# ESP32_RC522_ACS712_NUTNHAN_RELAY.net
KiCad netlist of a schematic drawn in EasyEDA
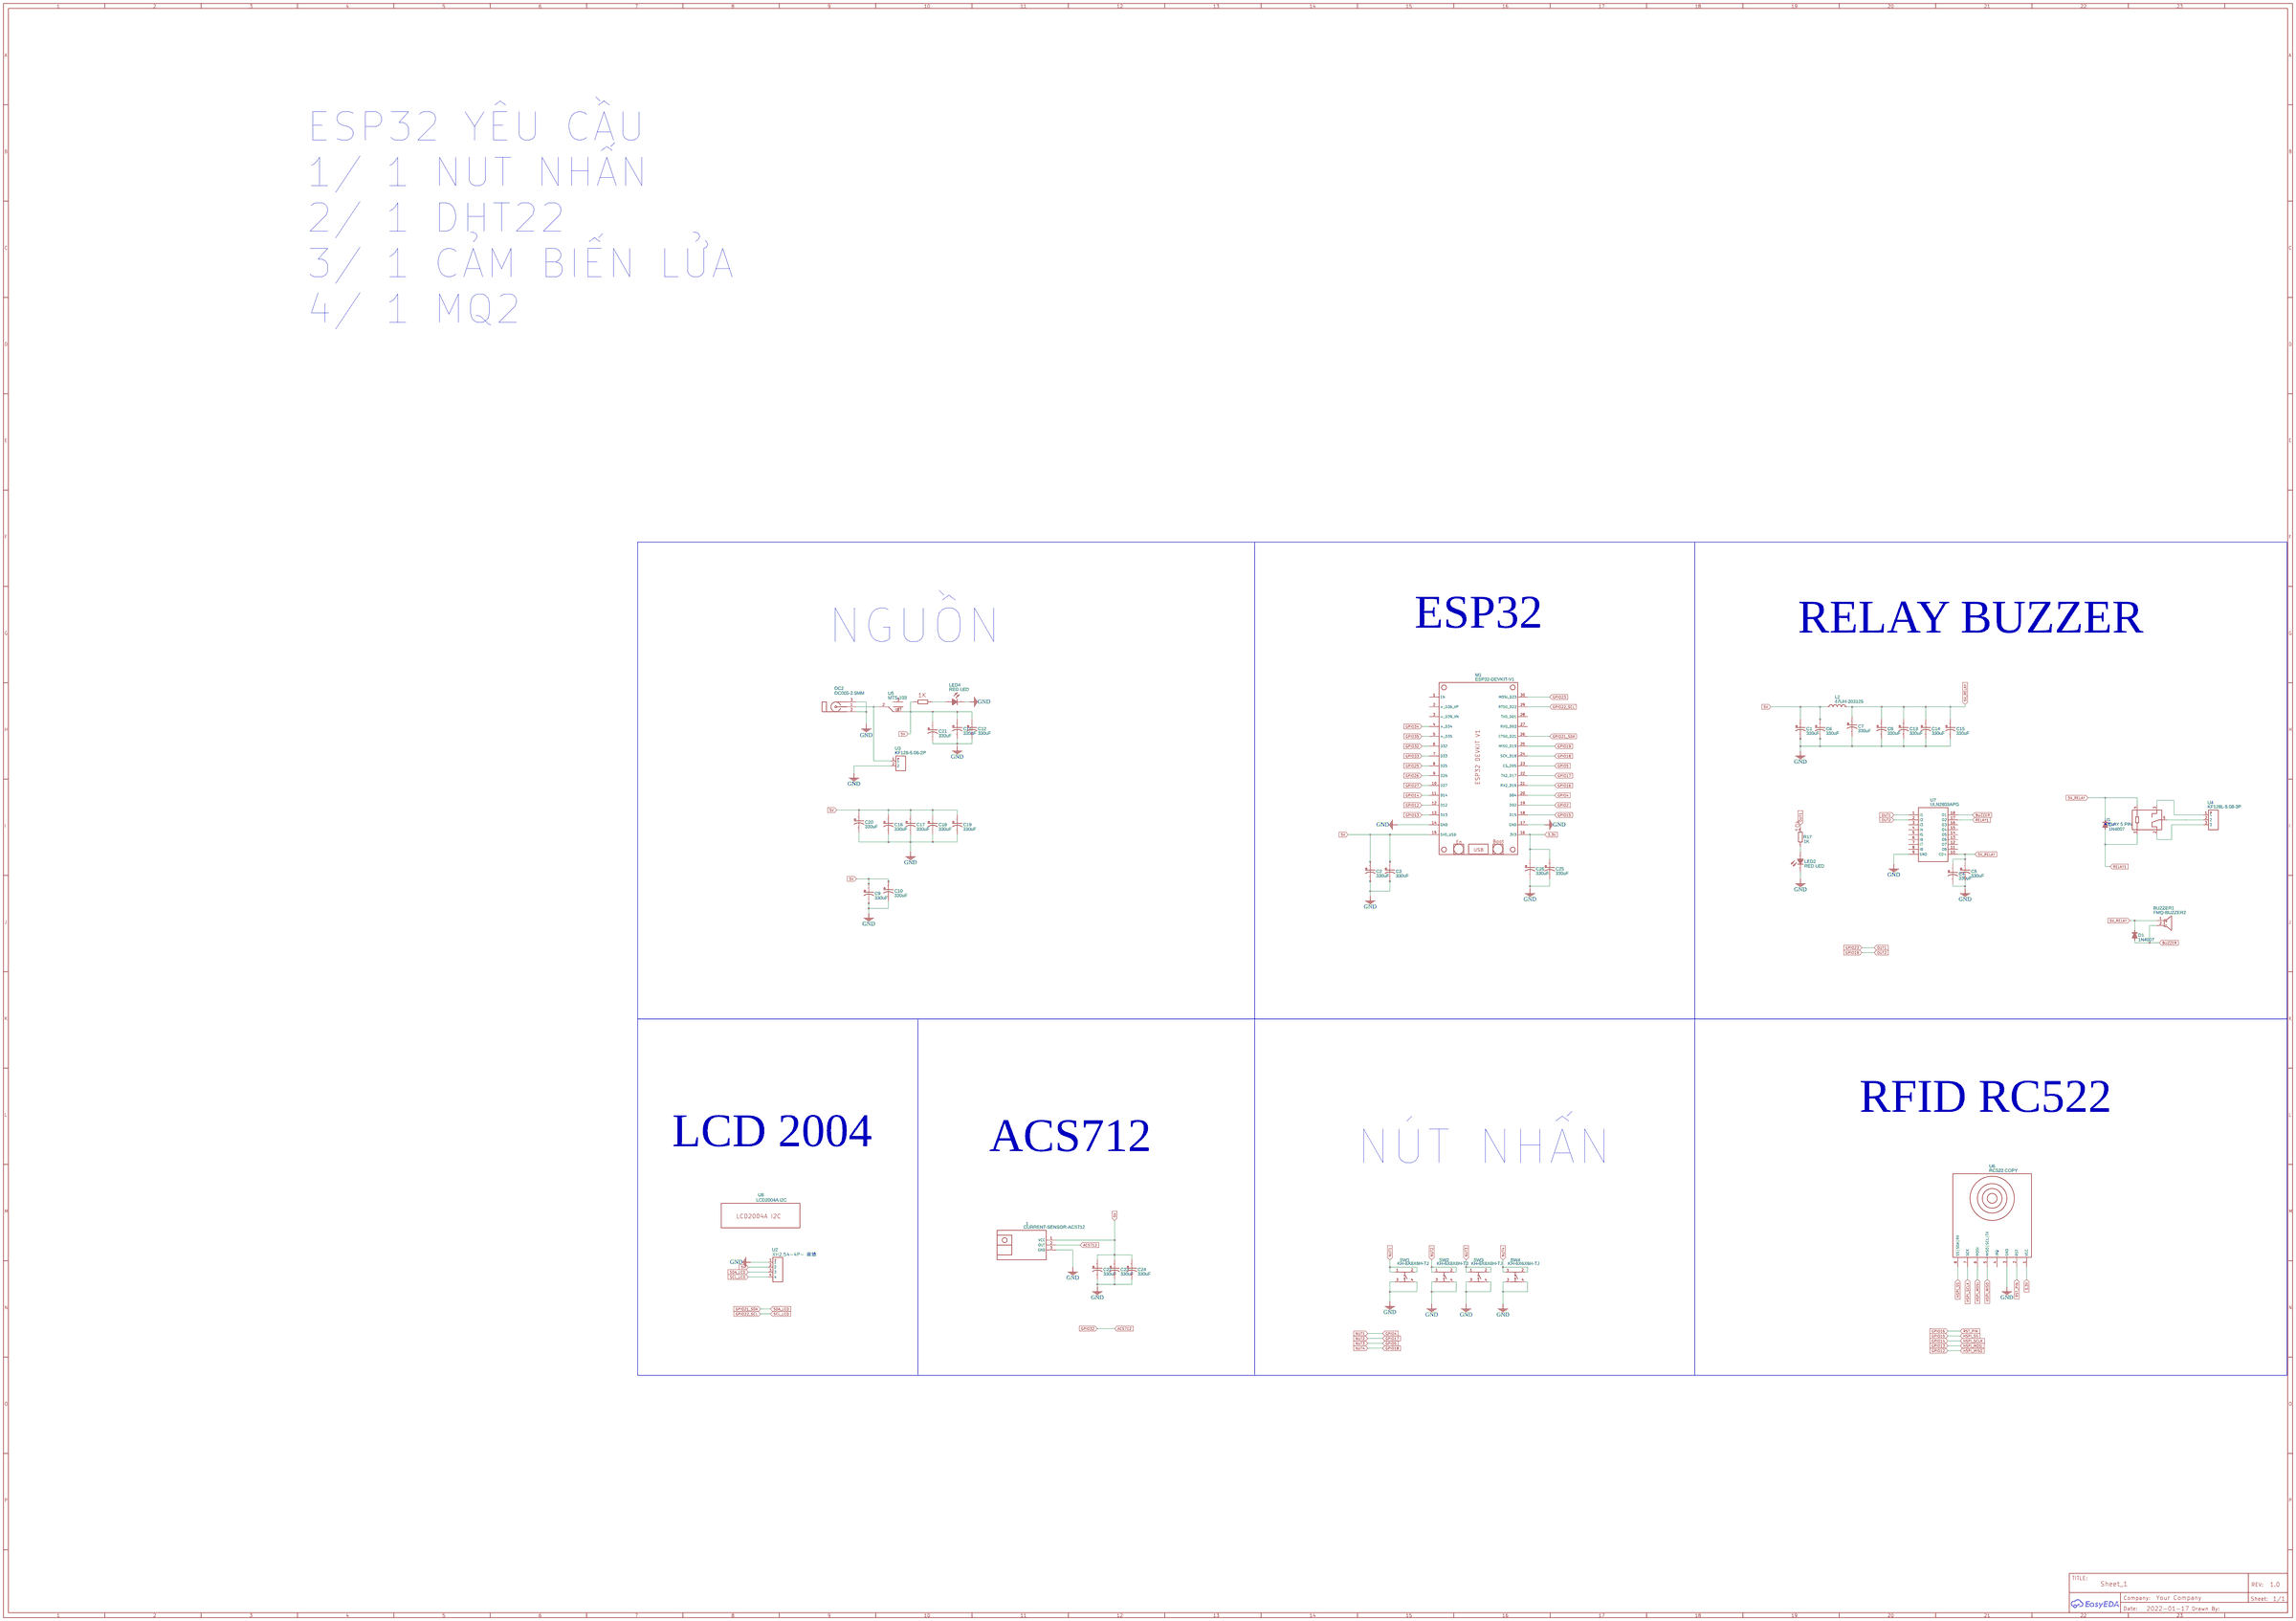
[diagram p0: schematic sheet]

(export (version "E")
  (design (tool "Eeschema 10.0.6"))
  (components
    (comp (ref "1") (value "CURRENT-SENSOR-ACS712") (libsource (lib "") (part "CURRENT-SENSOR-ACS712")))
    (comp (ref "BUZZER1")
      (value "FMQ-BUZZER2")
      (fields (field (name "BOM_Supplier Part") "C9900006103"))
      (libsource (lib "") (part "FMQ-BUZZER2"))
    )
    (comp (ref "C1")
      (value "330uF")
      (fields (field (name "BOM_Supplier Part") "C165541"))
      (libsource (lib "") (part "NXA 16V330 8*11.5"))
    )
    (comp (ref "C2")
      (value "330uF")
      (fields (field (name "BOM_Supplier Part") "C165541"))
      (libsource (lib "") (part "NXA 16V330 8*11.5"))
    )
    (comp (ref "C3")
      (value "330uF")
      (fields (field (name "BOM_Supplier Part") "C165541"))
      (libsource (lib "") (part "NXA 16V330 8*11.5"))
    )
    (comp (ref "C4")
      (value "330uF")
      (fields (field (name "BOM_Supplier Part") "C165541"))
      (libsource (lib "") (part "NXA 16V330 8*11.5"))
    )
    (comp (ref "C5")
      (value "330uF")
      (fields (field (name "BOM_Supplier Part") "C165541"))
      (libsource (lib "") (part "NXA 16V330 8*11.5"))
    )
    (comp (ref "C6")
      (value "330uF")
      (fields (field (name "BOM_Supplier Part") "C165541"))
      (libsource (lib "") (part "NXA 16V330 8*11.5"))
    )
    (comp (ref "C7")
      (value "330uF")
      (fields (field (name "BOM_Supplier Part") "C165541"))
      (libsource (lib "") (part "NXA 16V330 8*11.5"))
    )
    (comp (ref "C8")
      (value "330uF")
      (fields (field (name "BOM_Supplier Part") "C165541"))
      (libsource (lib "") (part "NXA 16V330 8*11.5"))
    )
    (comp (ref "C9")
      (value "330uF")
      (fields (field (name "BOM_Supplier Part") "C165541"))
      (libsource (lib "") (part "NXA 16V330 8*11.5"))
    )
    (comp (ref "C10")
      (value "330uF")
      (fields (field (name "BOM_Supplier Part") "C165541"))
      (libsource (lib "") (part "NXA 16V330 8*11.5"))
    )
    (comp (ref "C11")
      (value "330uF")
      (fields (field (name "BOM_Supplier Part") "C165541"))
      (libsource (lib "") (part "NXA 16V330 8*11.5"))
    )
    (comp (ref "C12")
      (value "330uF")
      (fields (field (name "BOM_Supplier Part") "C165541"))
      (libsource (lib "") (part "NXA 16V330 8*11.5"))
    )
    (comp (ref "C13")
      (value "330uF")
      (fields (field (name "BOM_Supplier Part") "C165541"))
      (libsource (lib "") (part "NXA 16V330 8*11.5"))
    )
    (comp (ref "C14")
      (value "330uF")
      (fields (field (name "BOM_Supplier Part") "C165541"))
      (libsource (lib "") (part "NXA 16V330 8*11.5"))
    )
    (comp (ref "C15")
      (value "330uF")
      (fields (field (name "BOM_Supplier Part") "C165541"))
      (libsource (lib "") (part "NXA 16V330 8*11.5"))
    )
    (comp (ref "C16")
      (value "330uF")
      (fields (field (name "BOM_Supplier Part") "C165541"))
      (libsource (lib "") (part "NXA 16V330 8*11.5"))
    )
    (comp (ref "C17")
      (value "330uF")
      (fields (field (name "BOM_Supplier Part") "C165541"))
      (libsource (lib "") (part "NXA 16V330 8*11.5"))
    )
    (comp (ref "C18")
      (value "330uF")
      (fields (field (name "BOM_Supplier Part") "C165541"))
      (libsource (lib "") (part "NXA 16V330 8*11.5"))
    )
    (comp (ref "C19")
      (value "330uF")
      (fields (field (name "BOM_Supplier Part") "C165541"))
      (libsource (lib "") (part "NXA 16V330 8*11.5"))
    )
    (comp (ref "C20")
      (value "330uF")
      (fields (field (name "BOM_Supplier Part") "C165541"))
      (libsource (lib "") (part "NXA 16V330 8*11.5"))
    )
    (comp (ref "C21")
      (value "330uF")
      (fields (field (name "BOM_Supplier Part") "C165541"))
      (libsource (lib "") (part "NXA 16V330 8*11.5"))
    )
    (comp (ref "C22")
      (value "330uF")
      (fields (field (name "BOM_Supplier Part") "C165541"))
      (libsource (lib "") (part "NXA 16V330 8*11.5_1"))
    )
    (comp (ref "C23")
      (value "330uF")
      (fields (field (name "BOM_Supplier Part") "C165541"))
      (libsource (lib "") (part "NXA 16V330 8*11.5_1"))
    )
    (comp (ref "C24")
      (value "330uF")
      (fields (field (name "BOM_Supplier Part") "C165541"))
      (libsource (lib "") (part "NXA 16V330 8*11.5_1"))
    )
    (comp (ref "C25")
      (value "330uF")
      (fields (field (name "BOM_Supplier Part") "C165541"))
      (libsource (lib "") (part "NXA 16V330 8*11.5"))
    )
    (comp (ref "C26")
      (value "330uF")
      (fields (field (name "BOM_Supplier Part") "C165541"))
      (libsource (lib "") (part "NXA 16V330 8*11.5"))
    )
    (comp (ref "D1") (value "1N4007") (libsource (lib "") (part "1N4007")))
    (comp (ref "D4") (value "1N4007") (libsource (lib "") (part "1N4007")))
    (comp (ref "DC2")
      (value "DC005-2.5MM")
      (fields (field (name "BOM_Supplier Part") "C111573"))
      (libsource (lib "") (part "DC005-2.5MM"))
    )
    (comp (ref "L2")
      (value "47UH-203125")
      (fields
        (field (name "BOM_Manufacturer Part") "47uH-203125")
        (field (name "BOM_Supplier Part") "C9900004701")
      )
      (libsource (lib "") (part "47UH-203125"))
    )
    (comp (ref "LED2")
      (value "RED LED")
      (fields
        (field (name "BOM_Manufacturer Part") "333-2SURD/S530-A3")
        (field (name "BOM_Supplier Part") "C87271")
      )
      (libsource (lib "") (part "RED LED"))
    )
    (comp (ref "LED4")
      (value "RED LED")
      (fields
        (field (name "BOM_Manufacturer Part") "333-2SURD/S530-A3")
        (field (name "BOM_Supplier Part") "C87271")
      )
      (libsource (lib "") (part "RED LED_1"))
    )
    (comp (ref "M1")
      (value "ESP32-DEVKIT-V1")
      (fields (field (name "BOM_Manufacturer Part") "ESP32 Module - Doit.am"))
      (libsource (lib "") (part "ESP32-DEVKIT-V1"))
    )
    (comp (ref "R2")
      (value "1K")
      (fields
        (field (name "BOM_Manufacturer Part") "EWWR0003J1K00T9")
        (field (name "BOM_Supplier Part") "C348856")
      )
      (libsource (lib "") (part "resistor 10k ohm_1"))
    )
    (comp (ref "R17")
      (value "1K")
      (fields
        (field (name "BOM_Manufacturer Part") "EWWR0003J1K00T9")
        (field (name "BOM_Supplier Part") "C348856")
      )
      (libsource (lib "") (part "resistor 10k ohm"))
    )
    (comp (ref "SW1")
      (value "KH-6X6X6H-TJ")
      (fields (field (name "BOM_Supplier Part") "C2837516"))
      (libsource (lib "") (part "KH-6X6X6H-TJ"))
    )
    (comp (ref "SW2")
      (value "KH-6X6X6H-TJ")
      (fields (field (name "BOM_Supplier Part") "C2837516"))
      (libsource (lib "") (part "KH-6X6X6H-TJ"))
    )
    (comp (ref "SW3")
      (value "KH-6X6X6H-TJ")
      (fields (field (name "BOM_Supplier Part") "C2837516"))
      (libsource (lib "") (part "KH-6X6X6H-TJ"))
    )
    (comp (ref "SW4")
      (value "KH-6X6X6H-TJ")
      (fields (field (name "BOM_Supplier Part") "C2837516"))
      (libsource (lib "") (part "KH-6X6X6H-TJ"))
    )
    (comp (ref "U1") (value "RELAY 5 PIN") (libsource (lib "") (part "RELAY 5 PIN")))
    (comp (ref "U2")
      (value "XH2.54-4P- 直插")
      (fields (field (name "BOM_Supplier Part") "C9900000103"))
      (libsource (lib "") (part "XH2.54-4P- 直插"))
    )
    (comp (ref "U3")
      (value "KF128-5.08-2P")
      (fields (field (name "BOM_Supplier Part") "C474952"))
      (libsource (lib "") (part "KF128-5.08-2P"))
    )
    (comp (ref "U4")
      (value "KF128L-5.08-3P")
      (fields (field (name "BOM_Supplier Part") "C474941"))
      (libsource (lib "") (part "KF128L-5.08-3P"))
    )
    (comp (ref "U5") (value "MTS-103") (libsource (lib "") (part "MTS-103")))
    (comp (ref "U6") (value "RC522 COPY") (libsource (lib "") (part "RC522 COPY")))
    (comp (ref "U7")
      (value "ULN2803APG")
      (fields (field (name "BOM_Supplier Part") "C5252"))
      (libsource (lib "") (part "ULN2803APG"))
    )
    (comp (ref "U8")
      (value "LCD2004A I2C")
      (fields (field (name "BOM_Manufacturer Part") "LCD2004A"))
      (libsource (lib "") (part "LCD2004A I2C"))
    )
  )
  (nets
    (net (code "1") (name "3.3V") (class "Default")
      (node (ref "C25") (pin "1") (pinfunction "1_1") (pintype "unspecified"))
      (node (ref "C26") (pin "1") (pinfunction "1_1") (pintype "unspecified"))
      (node (ref "M1") (pin "16") (pinfunction "3V3_16") (pintype "unspecified"))
      (node (ref "U6") (pin "1") (pinfunction "VCC_1") (pintype "unspecified"))
    )
    (net (code "2") (name "5V") (class "Default")
      (node (ref "1") (pin "1") (pinfunction "VCC_1") (pintype "bidirectional"))
      (node (ref "C1") (pin "1") (pinfunction "1_1") (pintype "unspecified"))
      (node (ref "C10") (pin "1") (pinfunction "1_1") (pintype "unspecified"))
      (node (ref "C11") (pin "1") (pinfunction "1_1") (pintype "unspecified"))
      (node (ref "C12") (pin "1") (pinfunction "1_1") (pintype "unspecified"))
      (node (ref "C16") (pin "1") (pinfunction "1_1") (pintype "unspecified"))
      (node (ref "C17") (pin "1") (pinfunction "1_1") (pintype "unspecified"))
      (node (ref "C18") (pin "1") (pinfunction "1_1") (pintype "unspecified"))
      (node (ref "C19") (pin "1") (pinfunction "1_1") (pintype "unspecified"))
      (node (ref "C2") (pin "1") (pinfunction "1_1") (pintype "unspecified"))
      (node (ref "C20") (pin "1") (pinfunction "1_1") (pintype "unspecified"))
      (node (ref "C21") (pin "1") (pinfunction "1_1") (pintype "unspecified"))
      (node (ref "C22") (pin "1") (pinfunction "1_1") (pintype "unspecified"))
      (node (ref "C23") (pin "1") (pinfunction "1_1") (pintype "unspecified"))
      (node (ref "C24") (pin "1") (pinfunction "1_1") (pintype "unspecified"))
      (node (ref "C3") (pin "1") (pinfunction "1_1") (pintype "unspecified"))
      (node (ref "C6") (pin "1") (pinfunction "1_1") (pintype "unspecified"))
      (node (ref "C9") (pin "1") (pinfunction "1_1") (pintype "unspecified"))
      (node (ref "L2") (pin "1") (pinfunction "1_1") (pintype "unspecified"))
      (node (ref "M1") (pin "15") (pinfunction "5V0_USB_15") (pintype "unspecified"))
      (node (ref "R2") (pin "1") (pinfunction "1_1") (pintype "unspecified"))
      (node (ref "U2") (pin "2") (pinfunction "2_2") (pintype "unspecified"))
      (node (ref "U5") (pin "1") (pinfunction "1_1") (pintype "unspecified"))
    )
    (net (code "3") (name "5V_RELAY") (class "Default")
      (node (ref "BUZZER1") (pin "1") (pinfunction "1_1") (pintype "unspecified"))
      (node (ref "C13") (pin "1") (pinfunction "1_1") (pintype "unspecified"))
      (node (ref "C14") (pin "1") (pinfunction "1_1") (pintype "unspecified"))
      (node (ref "C15") (pin "1") (pinfunction "1_1") (pintype "unspecified"))
      (node (ref "C4") (pin "1") (pinfunction "1_1") (pintype "unspecified"))
      (node (ref "C5") (pin "1") (pinfunction "1_1") (pintype "unspecified"))
      (node (ref "C7") (pin "1") (pinfunction "1_1") (pintype "unspecified"))
      (node (ref "C8") (pin "1") (pinfunction "1_1") (pintype "unspecified"))
      (node (ref "D1") (pin "K") (pinfunction "K_K") (pintype "bidirectional"))
      (node (ref "D4") (pin "K") (pinfunction "K_K") (pintype "bidirectional"))
      (node (ref "L2") (pin "2") (pinfunction "2_2") (pintype "unspecified"))
      (node (ref "U1") (pin "4") (pinfunction "4_4") (pintype "unspecified"))
      (node (ref "U7") (pin "10") (pinfunction "CD+_10") (pintype "unspecified"))
    )
    (net (code "4") (name "ACS712") (class "Default")
      (node (ref "1") (pin "2") (pinfunction "OUT_2") (pintype "bidirectional"))
      (node (ref "M1") (pin "6") (pinfunction "D32_6") (pintype "unspecified"))
    )
    (net (code "5") (name "BUZZER") (class "Default")
      (node (ref "BUZZER1") (pin "2") (pinfunction "2_2") (pintype "unspecified"))
      (node (ref "D1") (pin "A") (pinfunction "A_A") (pintype "bidirectional"))
      (node (ref "U7") (pin "18") (pinfunction "O1_18") (pintype "unspecified"))
    )
    (net (code "6") (name "GND") (class "Default")
      (node (ref "1") (pin "3") (pinfunction "GND_3") (pintype "bidirectional"))
      (node (ref "C1") (pin "2") (pinfunction "2_2") (pintype "unspecified"))
      (node (ref "C10") (pin "2") (pinfunction "2_2") (pintype "unspecified"))
      (node (ref "C11") (pin "2") (pinfunction "2_2") (pintype "unspecified"))
      (node (ref "C12") (pin "2") (pinfunction "2_2") (pintype "unspecified"))
      (node (ref "C13") (pin "2") (pinfunction "2_2") (pintype "unspecified"))
      (node (ref "C14") (pin "2") (pinfunction "2_2") (pintype "unspecified"))
      (node (ref "C15") (pin "2") (pinfunction "2_2") (pintype "unspecified"))
      (node (ref "C16") (pin "2") (pinfunction "2_2") (pintype "unspecified"))
      (node (ref "C17") (pin "2") (pinfunction "2_2") (pintype "unspecified"))
      (node (ref "C18") (pin "2") (pinfunction "2_2") (pintype "unspecified"))
      (node (ref "C19") (pin "2") (pinfunction "2_2") (pintype "unspecified"))
      (node (ref "C2") (pin "2") (pinfunction "2_2") (pintype "unspecified"))
      (node (ref "C20") (pin "2") (pinfunction "2_2") (pintype "unspecified"))
      (node (ref "C21") (pin "2") (pinfunction "2_2") (pintype "unspecified"))
      (node (ref "C22") (pin "2") (pinfunction "2_2") (pintype "unspecified"))
      (node (ref "C23") (pin "2") (pinfunction "2_2") (pintype "unspecified"))
      (node (ref "C24") (pin "2") (pinfunction "2_2") (pintype "unspecified"))
      (node (ref "C25") (pin "2") (pinfunction "2_2") (pintype "unspecified"))
      (node (ref "C26") (pin "2") (pinfunction "2_2") (pintype "unspecified"))
      (node (ref "C3") (pin "2") (pinfunction "2_2") (pintype "unspecified"))
      (node (ref "C4") (pin "2") (pinfunction "2_2") (pintype "unspecified"))
      (node (ref "C5") (pin "2") (pinfunction "2_2") (pintype "unspecified"))
      (node (ref "C6") (pin "2") (pinfunction "2_2") (pintype "unspecified"))
      (node (ref "C7") (pin "2") (pinfunction "2_2") (pintype "unspecified"))
      (node (ref "C8") (pin "2") (pinfunction "2_2") (pintype "unspecified"))
      (node (ref "C9") (pin "2") (pinfunction "2_2") (pintype "unspecified"))
      (node (ref "DC2") (pin "2") (pinfunction "2_2") (pintype "input"))
      (node (ref "DC2") (pin "3") (pinfunction "3_3") (pintype "input"))
      (node (ref "LED2") (pin "2") (pinfunction "C_2") (pintype "input"))
      (node (ref "LED4") (pin "2") (pinfunction "C_2") (pintype "input"))
      (node (ref "M1") (pin "14") (pinfunction "GND_14") (pintype "unspecified"))
      (node (ref "M1") (pin "17") (pinfunction "GND_17") (pintype "unspecified"))
      (node (ref "SW1") (pin "3") (pinfunction "3_3") (pintype "unspecified"))
      (node (ref "SW1") (pin "4") (pinfunction "4_4") (pintype "unspecified"))
      (node (ref "SW2") (pin "3") (pinfunction "3_3") (pintype "unspecified"))
      (node (ref "SW2") (pin "4") (pinfunction "4_4") (pintype "unspecified"))
      (node (ref "SW3") (pin "3") (pinfunction "3_3") (pintype "unspecified"))
      (node (ref "SW3") (pin "4") (pinfunction "4_4") (pintype "unspecified"))
      (node (ref "SW4") (pin "3") (pinfunction "3_3") (pintype "unspecified"))
      (node (ref "SW4") (pin "4") (pinfunction "4_4") (pintype "unspecified"))
      (node (ref "U2") (pin "1") (pinfunction "1_1") (pintype "unspecified"))
      (node (ref "U3") (pin "2") (pinfunction "2_2") (pintype "unspecified"))
      (node (ref "U6") (pin "3") (pinfunction "GND_3") (pintype "unspecified"))
      (node (ref "U7") (pin "9") (pinfunction "GND_9") (pintype "passive"))
    )
    (net (code "7") (name "GPIO2") (class "Default")
      (node (ref "M1") (pin "19") (pinfunction "D02_19") (pintype "unspecified"))
    )
    (net (code "8") (name "GPIO4") (class "Default")
      (node (ref "M1") (pin "20") (pinfunction "D04_20") (pintype "unspecified"))
      (node (ref "SW1") (pin "1") (pinfunction "1_1") (pintype "unspecified"))
      (node (ref "SW1") (pin "2") (pinfunction "2_2") (pintype "unspecified"))
    )
    (net (code "9") (name "GPIO5") (class "Default")
      (node (ref "M1") (pin "23") (pinfunction "CS_D05_23") (pintype "unspecified"))
      (node (ref "SW3") (pin "1") (pinfunction "1_1") (pintype "unspecified"))
      (node (ref "SW3") (pin "2") (pinfunction "2_2") (pintype "unspecified"))
    )
    (net (code "10") (name "GPIO12") (class "Default")
      (node (ref "M1") (pin "12") (pinfunction "D12_12") (pintype "unspecified"))
      (node (ref "U6") (pin "5") (pinfunction "MISO|SCL|TX_5") (pintype "unspecified"))
    )
    (net (code "11") (name "GPIO13") (class "Default")
      (node (ref "M1") (pin "13") (pinfunction "D13_13") (pintype "unspecified"))
      (node (ref "U6") (pin "6") (pinfunction "MOSI_6") (pintype "unspecified"))
    )
    (net (code "12") (name "GPIO14") (class "Default")
      (node (ref "M1") (pin "11") (pinfunction "D14_11") (pintype "unspecified"))
      (node (ref "U6") (pin "7") (pinfunction "SCK_7") (pintype "unspecified"))
    )
    (net (code "13") (name "GPIO15") (class "Default")
      (node (ref "M1") (pin "18") (pinfunction "D15_18") (pintype "unspecified"))
      (node (ref "U6") (pin "8") (pinfunction "SS|SDA|RX_8") (pintype "unspecified"))
    )
    (net (code "14") (name "GPIO16") (class "Default")
      (node (ref "M1") (pin "21") (pinfunction "RX2_D16_21") (pintype "unspecified"))
      (node (ref "U6") (pin "2") (pinfunction "RST_2") (pintype "unspecified"))
    )
    (net (code "15") (name "GPIO17") (class "Default")
      (node (ref "M1") (pin "22") (pinfunction "TX2_D17_22") (pintype "unspecified"))
      (node (ref "SW2") (pin "1") (pinfunction "1_1") (pintype "unspecified"))
      (node (ref "SW2") (pin "2") (pinfunction "2_2") (pintype "unspecified"))
    )
    (net (code "16") (name "GPIO18") (class "Default")
      (node (ref "M1") (pin "24") (pinfunction "SCK_D18_24") (pintype "unspecified"))
      (node (ref "SW4") (pin "1") (pinfunction "1_1") (pintype "unspecified"))
      (node (ref "SW4") (pin "2") (pinfunction "2_2") (pintype "unspecified"))
    )
    (net (code "17") (name "GPIO19") (class "Default")
      (node (ref "M1") (pin "25") (pinfunction "MISO_D19_25") (pintype "unspecified"))
      (node (ref "U7") (pin "2") (pinfunction "I2_2") (pintype "input"))
    )
    (net (code "18") (name "GPIO21_SDA") (class "Default")
      (node (ref "M1") (pin "26") (pinfunction "CTS0_D21_26") (pintype "unspecified"))
      (node (ref "U2") (pin "3") (pinfunction "3_3") (pintype "unspecified"))
    )
    (net (code "19") (name "GPIO22_SCL") (class "Default")
      (node (ref "M1") (pin "29") (pinfunction "RTS0_D22_29") (pintype "unspecified"))
      (node (ref "U2") (pin "4") (pinfunction "4_4") (pintype "unspecified"))
    )
    (net (code "20") (name "GPIO23") (class "Default")
      (node (ref "M1") (pin "30") (pinfunction "MOSI_D23_30") (pintype "unspecified"))
      (node (ref "R17") (pin "1") (pinfunction "1_1") (pintype "unspecified"))
      (node (ref "U7") (pin "1") (pinfunction "I1_1") (pintype "input"))
    )
    (net (code "21") (name "GPIO25") (class "Default")
      (node (ref "M1") (pin "8") (pinfunction "D25_8") (pintype "unspecified"))
    )
    (net (code "22") (name "GPIO26") (class "Default")
      (node (ref "M1") (pin "9") (pinfunction "D26_9") (pintype "unspecified"))
    )
    (net (code "23") (name "GPIO27") (class "Default")
      (node (ref "M1") (pin "10") (pinfunction "D27_10") (pintype "unspecified"))
    )
    (net (code "24") (name "GPIO33") (class "Default")
      (node (ref "M1") (pin "7") (pinfunction "D33_7") (pintype "unspecified"))
    )
    (net (code "25") (name "GPIO34") (class "Default")
      (node (ref "M1") (pin "4") (pinfunction ">_D34_4") (pintype "unspecified"))
    )
    (net (code "26") (name "GPIO35") (class "Default")
      (node (ref "M1") (pin "5") (pinfunction ">_D35_5") (pintype "unspecified"))
    )
    (net (code "27") (name "Net-(DC2-VCC)") (class "Default")
      (node (ref "DC2") (pin "1") (pinfunction "VCC_1") (pintype "input"))
      (node (ref "U3") (pin "1") (pinfunction "1_1") (pintype "unspecified"))
      (node (ref "U5") (pin "2") (pinfunction "2_2") (pintype "unspecified"))
    )
    (net (code "28") (name "Net-(LED2-A)") (class "Default")
      (node (ref "LED2") (pin "1") (pinfunction "A_1") (pintype "input"))
      (node (ref "R17") (pin "2") (pinfunction "2_2") (pintype "unspecified"))
    )
    (net (code "29") (name "Net-(LED4-A)") (class "Default")
      (node (ref "LED4") (pin "1") (pinfunction "A_1") (pintype "input"))
      (node (ref "R2") (pin "2") (pinfunction "2_2") (pintype "unspecified"))
    )
    (net (code "30") (name "Net-(U1-Pad2)") (class "Default")
      (node (ref "U1") (pin "2") (pinfunction "2_2") (pintype "unspecified"))
      (node (ref "U4") (pin "3") (pinfunction "3_3") (pintype "unspecified"))
    )
    (net (code "31") (name "Net-(U1-Pad3)") (class "Default")
      (node (ref "U1") (pin "3") (pinfunction "3_3") (pintype "unspecified"))
      (node (ref "U4") (pin "1") (pinfunction "1_1") (pintype "unspecified"))
    )
    (net (code "32") (name "Net-(U1-Pad5)") (class "Default")
      (node (ref "U1") (pin "5") (pinfunction "5_5") (pintype "unspecified"))
      (node (ref "U4") (pin "2") (pinfunction "2_2") (pintype "unspecified"))
    )
    (net (code "33") (name "RELAY1") (class "Default")
      (node (ref "D4") (pin "A") (pinfunction "A_A") (pintype "bidirectional"))
      (node (ref "U1") (pin "1") (pinfunction "1_1") (pintype "unspecified"))
      (node (ref "U7") (pin "17") (pinfunction "O2_17") (pintype "unspecified"))
    )
    (net (code "34") (name "unconnected-(M1->_D36_VP-Pad2)") (class "Default")
      (node (ref "M1") (pin "2") (pinfunction ">_D36_VP_2") (pintype "unspecified"))
    )
    (net (code "35") (name "unconnected-(M1->_D39_VN-Pad3)") (class "Default")
      (node (ref "M1") (pin "3") (pinfunction ">_D39_VN_3") (pintype "unspecified"))
    )
    (net (code "36") (name "unconnected-(M1-EN-Pad1)") (class "Default")
      (node (ref "M1") (pin "1") (pinfunction "EN_1") (pintype "unspecified"))
    )
    (net (code "37") (name "unconnected-(M1-RX0_D03-Pad27)") (class "Default")
      (node (ref "M1") (pin "27") (pinfunction "RX0_D03_27") (pintype "unspecified"))
    )
    (net (code "38") (name "unconnected-(M1-TX0_D01-Pad28)") (class "Default")
      (node (ref "M1") (pin "28") (pinfunction "TX0_D01_28") (pintype "unspecified"))
    )
    (net (code "39") (name "unconnected-(U5-Pad3)") (class "Default")
      (node (ref "U5") (pin "3") (pinfunction "3_3") (pintype "unspecified"))
    )
    (net (code "40") (name "unconnected-(U6-IRQ-Pad4)") (class "Default")
      (node (ref "U6") (pin "4") (pinfunction "IRQ_4") (pintype "unspecified"))
    )
    (net (code "41") (name "unconnected-(U7-I3-Pad3)") (class "Default")
      (node (ref "U7") (pin "3") (pinfunction "I3_3") (pintype "input"))
    )
    (net (code "42") (name "unconnected-(U7-I4-Pad4)") (class "Default")
      (node (ref "U7") (pin "4") (pinfunction "I4_4") (pintype "input"))
    )
    (net (code "43") (name "unconnected-(U7-I5-Pad5)") (class "Default")
      (node (ref "U7") (pin "5") (pinfunction "I5_5") (pintype "input"))
    )
    (net (code "44") (name "unconnected-(U7-I6-Pad6)") (class "Default")
      (node (ref "U7") (pin "6") (pinfunction "I6_6") (pintype "input"))
    )
    (net (code "45") (name "unconnected-(U7-I7-Pad7)") (class "Default")
      (node (ref "U7") (pin "7") (pinfunction "I7_7") (pintype "input"))
    )
    (net (code "46") (name "unconnected-(U7-I8-Pad8)") (class "Default")
      (node (ref "U7") (pin "8") (pinfunction "I8_8") (pintype "input"))
    )
    (net (code "47") (name "unconnected-(U7-O3-Pad16)") (class "Default")
      (node (ref "U7") (pin "16") (pinfunction "O3_16") (pintype "unspecified"))
    )
    (net (code "48") (name "unconnected-(U7-O4-Pad15)") (class "Default")
      (node (ref "U7") (pin "15") (pinfunction "O4_15") (pintype "unspecified"))
    )
    (net (code "49") (name "unconnected-(U7-O5-Pad14)") (class "Default")
      (node (ref "U7") (pin "14") (pinfunction "O5_14") (pintype "unspecified"))
    )
    (net (code "50") (name "unconnected-(U7-O6-Pad13)") (class "Default")
      (node (ref "U7") (pin "13") (pinfunction "O6_13") (pintype "unspecified"))
    )
    (net (code "51") (name "unconnected-(U7-O7-Pad12)") (class "Default")
      (node (ref "U7") (pin "12") (pinfunction "O7_12") (pintype "unspecified"))
    )
    (net (code "52") (name "unconnected-(U7-O8-Pad11)") (class "Default")
      (node (ref "U7") (pin "11") (pinfunction "O8_11") (pintype "unspecified"))
    )
  )
)
